# motor-control-board.net
KiCad netlist of a schematic drawn in EAGLE
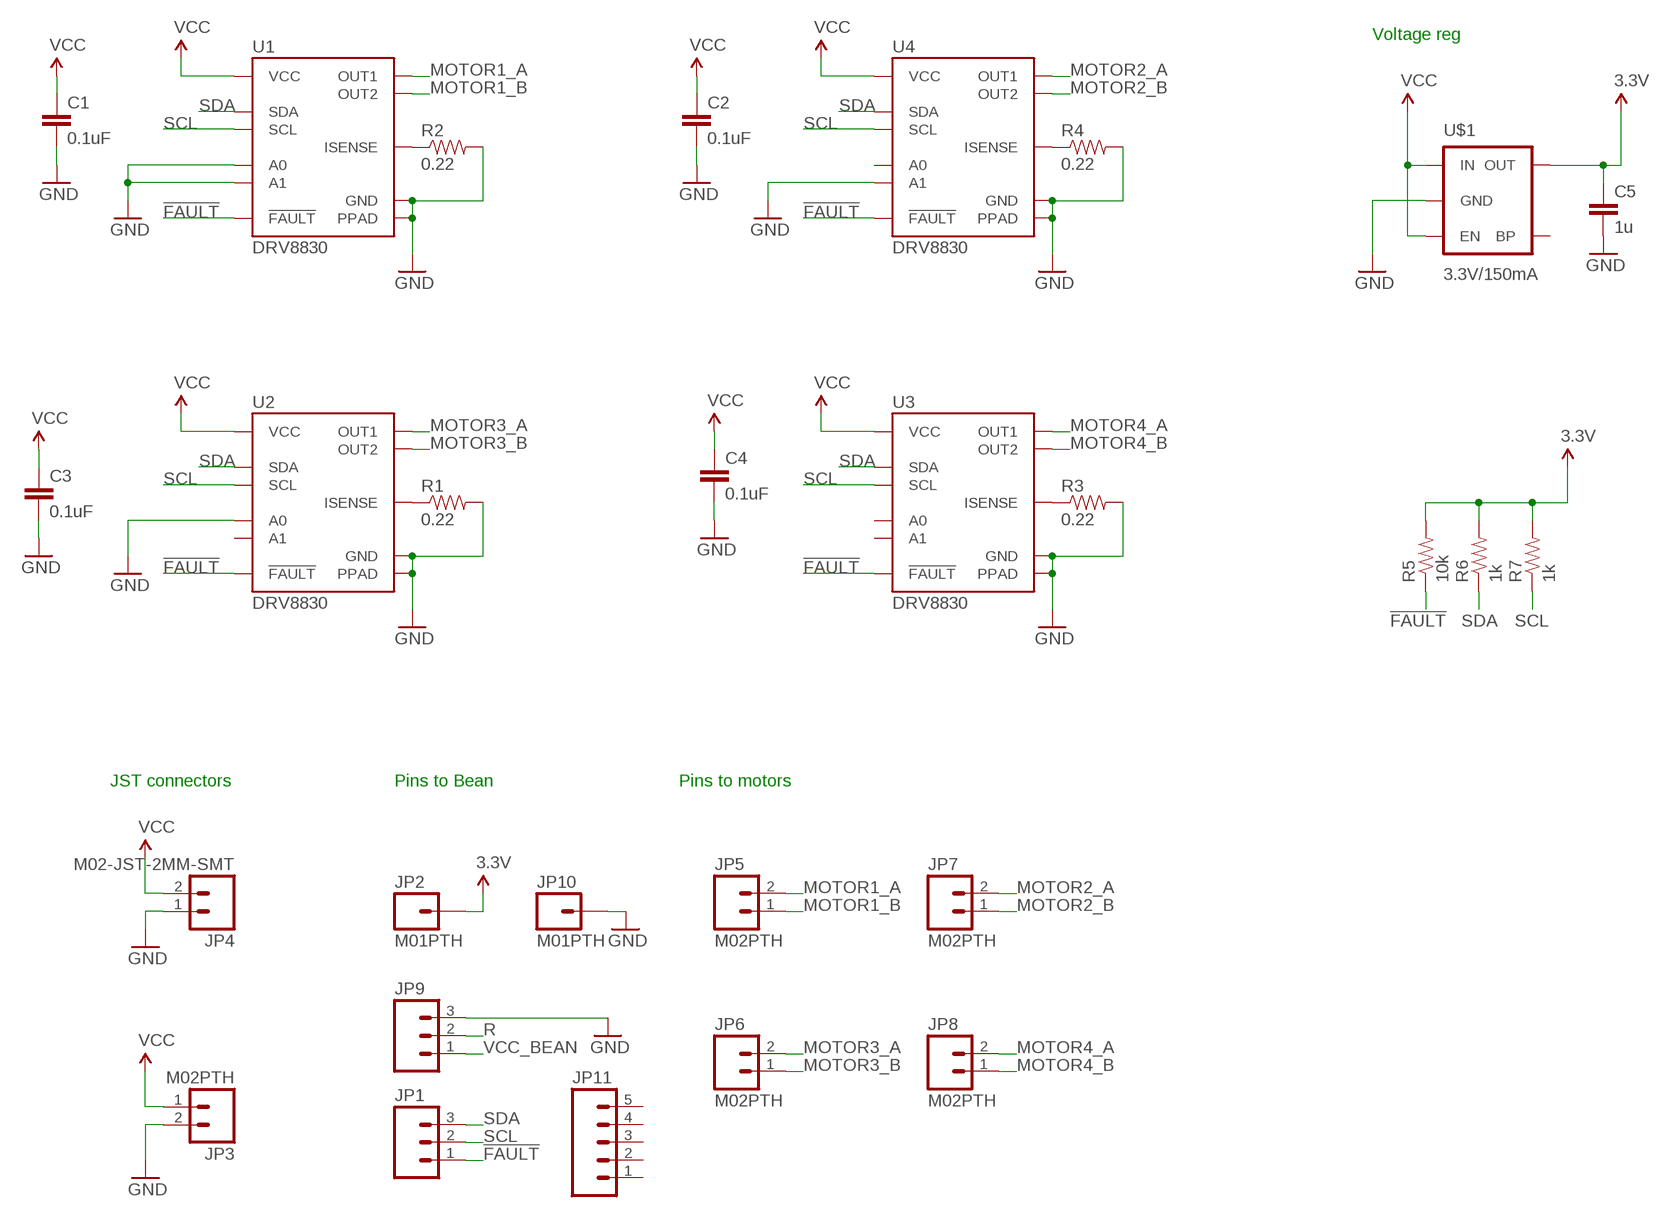
[diagram p0: schematic, sheet 1]

(export (version "E")
  (design (tool "Eeschema 10.0.6"))
  (components
    (comp (ref "C1")
      (value "0.1uF")
      (footprint "eagle-import:0402-CAP")
      (libsource (lib "eagle-import") (part "0.1UF-16V(+-10%)(0402)"))
    )
    (comp (ref "C2")
      (value "0.1uF")
      (footprint "eagle-import:0402-CAP")
      (libsource (lib "eagle-import") (part "0.1UF-16V(+-10%)(0402)"))
    )
    (comp (ref "C3")
      (value "0.1uF")
      (footprint "eagle-import:0402-CAP")
      (libsource (lib "eagle-import") (part "0.1UF-16V(+-10%)(0402)"))
    )
    (comp (ref "C4")
      (value "0.1uF")
      (footprint "eagle-import:0402-CAP")
      (libsource (lib "eagle-import") (part "CAP0402-CAP"))
    )
    (comp (ref "C5")
      (value "1u")
      (footprint "eagle-import:0402-CAP")
      (libsource (lib "eagle-import") (part "CAP0402-CAP"))
    )
    (comp (ref "JP1")
      (value "M03PTH")
      (footprint "eagle-import:1X03")
      (libsource (lib "eagle-import") (part "M03PTH"))
    )
    (comp (ref "JP2")
      (value "M01PTH")
      (footprint "eagle-import:1X01")
      (libsource (lib "eagle-import") (part "M01PTH"))
    )
    (comp (ref "JP3")
      (value "M02PTH")
      (footprint "eagle-import:1X02")
      (libsource (lib "eagle-import") (part "M02PTH"))
    )
    (comp (ref "JP4")
      (value "M02-JST-2MM-SMT")
      (footprint "eagle-import:JST-2-SMD")
      (libsource (lib "eagle-import") (part "M02-JST-2MM-SMT"))
    )
    (comp (ref "JP5")
      (value "M02PTH")
      (footprint "eagle-import:1X02")
      (libsource (lib "eagle-import") (part "M02PTH"))
    )
    (comp (ref "JP6")
      (value "M02PTH")
      (footprint "eagle-import:1X02")
      (libsource (lib "eagle-import") (part "M02PTH"))
    )
    (comp (ref "JP7")
      (value "M02PTH")
      (footprint "eagle-import:1X02")
      (libsource (lib "eagle-import") (part "M02PTH"))
    )
    (comp (ref "JP8")
      (value "M02PTH")
      (footprint "eagle-import:1X02")
      (libsource (lib "eagle-import") (part "M02PTH"))
    )
    (comp (ref "JP9")
      (value "M03PTH")
      (footprint "eagle-import:1X03")
      (libsource (lib "eagle-import") (part "M03PTH"))
    )
    (comp (ref "JP10")
      (value "M01PTH")
      (footprint "eagle-import:1X01")
      (libsource (lib "eagle-import") (part "M01PTH"))
    )
    (comp (ref "JP11")
      (value "M05PTH")
      (footprint "eagle-import:1X05")
      (libsource (lib "eagle-import") (part "M05PTH"))
    )
    (comp (ref "R1")
      (value "0.22")
      (footprint "eagle-import:0805")
      (libsource (lib "eagle-import") (part "RESISTOR0805-RES"))
    )
    (comp (ref "R2")
      (value "0.22")
      (footprint "eagle-import:0805")
      (libsource (lib "eagle-import") (part "RESISTOR0805-RES"))
    )
    (comp (ref "R3")
      (value "0.22")
      (footprint "eagle-import:0805")
      (libsource (lib "eagle-import") (part "RESISTOR0805-RES"))
    )
    (comp (ref "R4")
      (value "0.22")
      (footprint "eagle-import:0805")
      (libsource (lib "eagle-import") (part "RESISTOR0805-RES"))
    )
    (comp (ref "R5")
      (value "10k")
      (footprint "eagle-import:0402-RES")
      (libsource (lib "eagle-import") (part "RESISTOR0402"))
    )
    (comp (ref "R6")
      (value "1k")
      (footprint "eagle-import:0402-RES")
      (libsource (lib "eagle-import") (part "RESISTOR0402"))
    )
    (comp (ref "R7")
      (value "1k")
      (footprint "eagle-import:0402-RES")
      (libsource (lib "eagle-import") (part "RESISTOR0402"))
    )
    (comp (ref "U$1")
      (value "3.3V/150mA")
      (footprint "eagle-import:SOT23-5")
      (libsource (lib "eagle-import") (part "V_REG_MIC52053.3V"))
    )
    (comp (ref "U1")
      (value "DRV8830")
      (footprint "eagle-import:MSOP-10-GNDPAD")
      (libsource (lib "eagle-import") (part "DRV8830"))
    )
    (comp (ref "U2")
      (value "DRV8830")
      (footprint "eagle-import:MSOP-10-GNDPAD")
      (libsource (lib "eagle-import") (part "DRV8830"))
    )
    (comp (ref "U3")
      (value "DRV8830")
      (footprint "eagle-import:MSOP-10-GNDPAD")
      (libsource (lib "eagle-import") (part "DRV8830"))
    )
    (comp (ref "U4")
      (value "DRV8830")
      (footprint "eagle-import:MSOP-10-GNDPAD")
      (libsource (lib "eagle-import") (part "DRV8830"))
    )
  )
  (nets
    (net (code "1") (name "/MOTOR1_A") (class "Default")
      (node (ref "JP5") (pin "2") (pinfunction "2_2") (pintype "passive"))
      (node (ref "U1") (pin "3") (pinfunction "OUT1_3") (pintype "power_in"))
    )
    (net (code "2") (name "/MOTOR1_B") (class "Default")
      (node (ref "JP5") (pin "1") (pinfunction "1_1") (pintype "passive"))
      (node (ref "U1") (pin "1") (pinfunction "OUT2_1") (pintype "power_in"))
    )
    (net (code "3") (name "/MOTOR2_A") (class "Default")
      (node (ref "JP7") (pin "2") (pinfunction "2_2") (pintype "passive"))
      (node (ref "U4") (pin "3") (pinfunction "OUT1_3") (pintype "power_in"))
    )
    (net (code "4") (name "/MOTOR2_B") (class "Default")
      (node (ref "JP7") (pin "1") (pinfunction "1_1") (pintype "passive"))
      (node (ref "U4") (pin "1") (pinfunction "OUT2_1") (pintype "power_in"))
    )
    (net (code "5") (name "/MOTOR3_A") (class "Default")
      (node (ref "JP6") (pin "2") (pinfunction "2_2") (pintype "passive"))
      (node (ref "U2") (pin "3") (pinfunction "OUT1_3") (pintype "power_in"))
    )
    (net (code "6") (name "/MOTOR3_B") (class "Default")
      (node (ref "JP6") (pin "1") (pinfunction "1_1") (pintype "passive"))
      (node (ref "U2") (pin "1") (pinfunction "OUT2_1") (pintype "power_in"))
    )
    (net (code "7") (name "/MOTOR4_A") (class "Default")
      (node (ref "JP8") (pin "2") (pinfunction "2_2") (pintype "passive"))
      (node (ref "U3") (pin "3") (pinfunction "OUT1_3") (pintype "power_in"))
    )
    (net (code "8") (name "/MOTOR4_B") (class "Default")
      (node (ref "JP8") (pin "1") (pinfunction "1_1") (pintype "passive"))
      (node (ref "U3") (pin "1") (pinfunction "OUT2_1") (pintype "power_in"))
    )
    (net (code "9") (name "/R") (class "Default")
      (node (ref "JP9") (pin "2") (pinfunction "2_2") (pintype "passive"))
    )
    (net (code "10") (name "/SCL") (class "Default")
      (node (ref "JP1") (pin "2") (pinfunction "2_2") (pintype "passive"))
      (node (ref "R7") (pin "1") (pinfunction "1_1") (pintype "passive"))
      (node (ref "U1") (pin "10") (pinfunction "SCL_10") (pintype "input"))
      (node (ref "U2") (pin "10") (pinfunction "SCL_10") (pintype "input"))
      (node (ref "U3") (pin "10") (pinfunction "SCL_10") (pintype "input"))
      (node (ref "U4") (pin "10") (pinfunction "SCL_10") (pintype "input"))
    )
    (net (code "11") (name "/SDA") (class "Default")
      (node (ref "JP1") (pin "3") (pinfunction "3_3") (pintype "passive"))
      (node (ref "R6") (pin "1") (pinfunction "1_1") (pintype "passive"))
      (node (ref "U1") (pin "9") (pinfunction "SDA_9") (pintype "bidirectional"))
      (node (ref "U2") (pin "9") (pinfunction "SDA_9") (pintype "bidirectional"))
      (node (ref "U3") (pin "9") (pinfunction "SDA_9") (pintype "bidirectional"))
      (node (ref "U4") (pin "9") (pinfunction "SDA_9") (pintype "bidirectional"))
    )
    (net (code "12") (name "/VCC_BEAN") (class "Default")
      (node (ref "JP9") (pin "1") (pinfunction "1_1") (pintype "passive"))
    )
    (net (code "13") (name "/~{FAULT}") (class "Default")
      (node (ref "JP1") (pin "1") (pinfunction "1_1") (pintype "passive"))
      (node (ref "R5") (pin "1") (pinfunction "1_1") (pintype "passive"))
      (node (ref "U1") (pin "6") (pinfunction "~{FAULT}_6") (pintype "output"))
      (node (ref "U2") (pin "6") (pinfunction "~{FAULT}_6") (pintype "output"))
      (node (ref "U3") (pin "6") (pinfunction "~{FAULT}_6") (pintype "output"))
      (node (ref "U4") (pin "6") (pinfunction "~{FAULT}_6") (pintype "output"))
    )
    (net (code "14") (name "3.3V") (class "Default")
      (node (ref "C5") (pin "1") (pinfunction "1_1") (pintype "passive"))
      (node (ref "JP2") (pin "1") (pinfunction "1_1") (pintype "passive"))
      (node (ref "R5") (pin "2") (pinfunction "2_2") (pintype "passive"))
      (node (ref "R6") (pin "2") (pinfunction "2_2") (pintype "passive"))
      (node (ref "R7") (pin "2") (pinfunction "2_2") (pintype "passive"))
      (node (ref "U$1") (pin "5") (pinfunction "OUT_5") (pintype "passive"))
    )
    (net (code "15") (name "GND") (class "Default")
      (node (ref "C1") (pin "2") (pinfunction "2_2") (pintype "passive"))
      (node (ref "C2") (pin "2") (pinfunction "2_2") (pintype "passive"))
      (node (ref "C3") (pin "2") (pinfunction "2_2") (pintype "passive"))
      (node (ref "C4") (pin "2") (pinfunction "2_2") (pintype "passive"))
      (node (ref "C5") (pin "2") (pinfunction "2_2") (pintype "passive"))
      (node (ref "JP10") (pin "1") (pinfunction "1_1") (pintype "passive"))
      (node (ref "JP3") (pin "2") (pinfunction "2_2") (pintype "passive"))
      (node (ref "JP4") (pin "1") (pinfunction "2_1") (pintype "passive"))
      (node (ref "JP9") (pin "3") (pinfunction "3_3") (pintype "passive"))
      (node (ref "R1") (pin "2") (pinfunction "2_2") (pintype "passive"))
      (node (ref "R2") (pin "2") (pinfunction "2_2") (pintype "passive"))
      (node (ref "R3") (pin "2") (pinfunction "2_2") (pintype "passive"))
      (node (ref "R4") (pin "2") (pinfunction "2_2") (pintype "passive"))
      (node (ref "U$1") (pin "2") (pinfunction "GND_2") (pintype "input"))
      (node (ref "U1") (pin "5") (pinfunction "GND_5") (pintype "power_in"))
      (node (ref "U1") (pin "7") (pinfunction "A0_7") (pintype "input"))
      (node (ref "U1") (pin "8") (pinfunction "A1_8") (pintype "input"))
      (node (ref "U1") (pin "GND") (pinfunction "PPAD_GND") (pintype "power_in"))
      (node (ref "U2") (pin "5") (pinfunction "GND_5") (pintype "power_in"))
      (node (ref "U2") (pin "7") (pinfunction "A0_7") (pintype "input"))
      (node (ref "U2") (pin "GND") (pinfunction "PPAD_GND") (pintype "power_in"))
      (node (ref "U3") (pin "5") (pinfunction "GND_5") (pintype "power_in"))
      (node (ref "U3") (pin "GND") (pinfunction "PPAD_GND") (pintype "power_in"))
      (node (ref "U4") (pin "5") (pinfunction "GND_5") (pintype "power_in"))
      (node (ref "U4") (pin "8") (pinfunction "A1_8") (pintype "input"))
      (node (ref "U4") (pin "GND") (pinfunction "PPAD_GND") (pintype "power_in"))
    )
    (net (code "16") (name "Net-(U1-ISENSE)") (class "Default")
      (node (ref "R2") (pin "1") (pinfunction "1_1") (pintype "passive"))
      (node (ref "U1") (pin "2") (pinfunction "ISENSE_2") (pintype "bidirectional"))
    )
    (net (code "17") (name "Net-(U2-ISENSE)") (class "Default")
      (node (ref "R1") (pin "1") (pinfunction "1_1") (pintype "passive"))
      (node (ref "U2") (pin "2") (pinfunction "ISENSE_2") (pintype "bidirectional"))
    )
    (net (code "18") (name "Net-(U3-ISENSE)") (class "Default")
      (node (ref "R3") (pin "1") (pinfunction "1_1") (pintype "passive"))
      (node (ref "U3") (pin "2") (pinfunction "ISENSE_2") (pintype "bidirectional"))
    )
    (net (code "19") (name "Net-(U4-ISENSE)") (class "Default")
      (node (ref "R4") (pin "1") (pinfunction "1_1") (pintype "passive"))
      (node (ref "U4") (pin "2") (pinfunction "ISENSE_2") (pintype "bidirectional"))
    )
    (net (code "20") (name "VCC") (class "Default")
      (node (ref "C1") (pin "1") (pinfunction "1_1") (pintype "passive"))
      (node (ref "C2") (pin "1") (pinfunction "1_1") (pintype "passive"))
      (node (ref "C3") (pin "1") (pinfunction "1_1") (pintype "passive"))
      (node (ref "C4") (pin "1") (pinfunction "1_1") (pintype "passive"))
      (node (ref "JP3") (pin "1") (pinfunction "1_1") (pintype "passive"))
      (node (ref "JP4") (pin "2") (pinfunction "1_2") (pintype "passive"))
      (node (ref "U$1") (pin "1") (pinfunction "IN_1") (pintype "input"))
      (node (ref "U$1") (pin "3") (pinfunction "EN_3") (pintype "input"))
      (node (ref "U1") (pin "4") (pinfunction "VCC_4") (pintype "power_in"))
      (node (ref "U2") (pin "4") (pinfunction "VCC_4") (pintype "power_in"))
      (node (ref "U3") (pin "4") (pinfunction "VCC_4") (pintype "power_in"))
      (node (ref "U4") (pin "4") (pinfunction "VCC_4") (pintype "power_in"))
    )
    (net (code "21") (name "unconnected-(JP11-Pad1)") (class "Default")
      (node (ref "JP11") (pin "1") (pinfunction "1_1") (pintype "passive"))
    )
    (net (code "22") (name "unconnected-(JP11-Pad2)") (class "Default")
      (node (ref "JP11") (pin "2") (pinfunction "2_2") (pintype "passive"))
    )
    (net (code "23") (name "unconnected-(JP11-Pad3)") (class "Default")
      (node (ref "JP11") (pin "3") (pinfunction "3_3") (pintype "passive"))
    )
    (net (code "24") (name "unconnected-(JP11-Pad4)") (class "Default")
      (node (ref "JP11") (pin "4") (pinfunction "4_4") (pintype "passive"))
    )
    (net (code "25") (name "unconnected-(JP11-Pad5)") (class "Default")
      (node (ref "JP11") (pin "5") (pinfunction "5_5") (pintype "passive"))
    )
    (net (code "26") (name "unconnected-(U$1-BP-Pad4)") (class "Default")
      (node (ref "U$1") (pin "4") (pinfunction "BP_4") (pintype "input"))
    )
    (net (code "27") (name "unconnected-(U2-A1-Pad8)") (class "Default")
      (node (ref "U2") (pin "8") (pinfunction "A1_8") (pintype "input"))
    )
    (net (code "28") (name "unconnected-(U3-A0-Pad7)") (class "Default")
      (node (ref "U3") (pin "7") (pinfunction "A0_7") (pintype "input"))
    )
    (net (code "29") (name "unconnected-(U3-A1-Pad8)") (class "Default")
      (node (ref "U3") (pin "8") (pinfunction "A1_8") (pintype "input"))
    )
    (net (code "30") (name "unconnected-(U4-A0-Pad7)") (class "Default")
      (node (ref "U4") (pin "7") (pinfunction "A0_7") (pintype "input"))
    )
  )
)
